# pokey.net
KiCad netlist of a schematic drawn in EAGLE
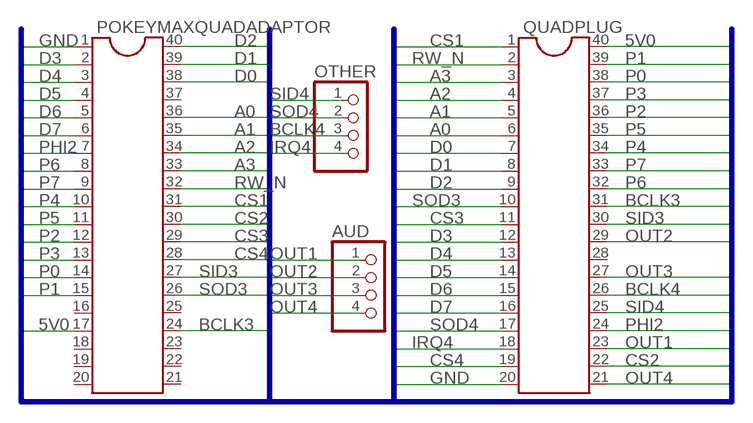
[diagram p0: schematic, sheet 1]

(export (version "E")
  (design (tool "Eeschema 10.0.6"))
  (components
    (comp (ref "AUD")
      (value "PINHD-1X4")
      (footprint "eagle-import:1X04")
      (libsource (lib "eagle-import") (part "PINHD-1X4"))
    )
    (comp (ref "OTHER")
      (value "PINHD-1X4")
      (footprint "eagle-import:1X04")
      (libsource (lib "eagle-import") (part "PINHD-1X4"))
    )
    (comp (ref "POKEYMAXQUADADAPTOR")
      (value "DIL40")
      (footprint "eagle-import:DIL40")
      (libsource (lib "eagle-import") (part "DIL40"))
    )
    (comp (ref "QUADPLUG")
      (value "DIL40")
      (footprint "eagle-import:DIL40")
      (libsource (lib "eagle-import") (part "DIL40"))
    )
  )
  (nets
    (net (code "1") (name "/5V0") (class "Default")
      (node (ref "POKEYMAXQUADADAPTOR") (pin "17") (pinfunction "17_17") (pintype "passive"))
      (node (ref "QUADPLUG") (pin "40") (pinfunction "40_40") (pintype "passive"))
    )
    (net (code "2") (name "/A0") (class "Default")
      (node (ref "POKEYMAXQUADADAPTOR") (pin "36") (pinfunction "36_36") (pintype "passive"))
      (node (ref "QUADPLUG") (pin "6") (pinfunction "6_6") (pintype "passive"))
    )
    (net (code "3") (name "/A1") (class "Default")
      (node (ref "POKEYMAXQUADADAPTOR") (pin "35") (pinfunction "35_35") (pintype "passive"))
      (node (ref "QUADPLUG") (pin "5") (pinfunction "5_5") (pintype "passive"))
    )
    (net (code "4") (name "/A2") (class "Default")
      (node (ref "POKEYMAXQUADADAPTOR") (pin "34") (pinfunction "34_34") (pintype "passive"))
      (node (ref "QUADPLUG") (pin "4") (pinfunction "4_4") (pintype "passive"))
    )
    (net (code "5") (name "/A3") (class "Default")
      (node (ref "POKEYMAXQUADADAPTOR") (pin "33") (pinfunction "33_33") (pintype "passive"))
      (node (ref "QUADPLUG") (pin "3") (pinfunction "3_3") (pintype "passive"))
    )
    (net (code "6") (name "/BCLK3") (class "Default")
      (node (ref "POKEYMAXQUADADAPTOR") (pin "24") (pinfunction "24_24") (pintype "passive"))
      (node (ref "QUADPLUG") (pin "31") (pinfunction "31_31") (pintype "passive"))
    )
    (net (code "7") (name "/BCLK4") (class "Default")
      (node (ref "OTHER") (pin "3") (pinfunction "3_3") (pintype "passive"))
      (node (ref "QUADPLUG") (pin "26") (pinfunction "26_26") (pintype "passive"))
    )
    (net (code "8") (name "/CS1") (class "Default")
      (node (ref "POKEYMAXQUADADAPTOR") (pin "31") (pinfunction "31_31") (pintype "passive"))
      (node (ref "QUADPLUG") (pin "1") (pinfunction "1_1") (pintype "passive"))
    )
    (net (code "9") (name "/CS2") (class "Default")
      (node (ref "POKEYMAXQUADADAPTOR") (pin "30") (pinfunction "30_30") (pintype "passive"))
      (node (ref "QUADPLUG") (pin "22") (pinfunction "22_22") (pintype "passive"))
    )
    (net (code "10") (name "/CS3") (class "Default")
      (node (ref "POKEYMAXQUADADAPTOR") (pin "29") (pinfunction "29_29") (pintype "passive"))
      (node (ref "QUADPLUG") (pin "11") (pinfunction "11_11") (pintype "passive"))
    )
    (net (code "11") (name "/CS4") (class "Default")
      (node (ref "POKEYMAXQUADADAPTOR") (pin "28") (pinfunction "28_28") (pintype "passive"))
      (node (ref "QUADPLUG") (pin "19") (pinfunction "19_19") (pintype "passive"))
    )
    (net (code "12") (name "/D0") (class "Default")
      (node (ref "POKEYMAXQUADADAPTOR") (pin "38") (pinfunction "38_38") (pintype "passive"))
      (node (ref "QUADPLUG") (pin "7") (pinfunction "7_7") (pintype "passive"))
    )
    (net (code "13") (name "/D1") (class "Default")
      (node (ref "POKEYMAXQUADADAPTOR") (pin "39") (pinfunction "39_39") (pintype "passive"))
      (node (ref "QUADPLUG") (pin "8") (pinfunction "8_8") (pintype "passive"))
    )
    (net (code "14") (name "/D2") (class "Default")
      (node (ref "POKEYMAXQUADADAPTOR") (pin "40") (pinfunction "40_40") (pintype "passive"))
      (node (ref "QUADPLUG") (pin "9") (pinfunction "9_9") (pintype "passive"))
    )
    (net (code "15") (name "/D3") (class "Default")
      (node (ref "POKEYMAXQUADADAPTOR") (pin "2") (pinfunction "2_2") (pintype "passive"))
      (node (ref "QUADPLUG") (pin "12") (pinfunction "12_12") (pintype "passive"))
    )
    (net (code "16") (name "/D4") (class "Default")
      (node (ref "POKEYMAXQUADADAPTOR") (pin "3") (pinfunction "3_3") (pintype "passive"))
      (node (ref "QUADPLUG") (pin "13") (pinfunction "13_13") (pintype "passive"))
    )
    (net (code "17") (name "/D5") (class "Default")
      (node (ref "POKEYMAXQUADADAPTOR") (pin "4") (pinfunction "4_4") (pintype "passive"))
      (node (ref "QUADPLUG") (pin "14") (pinfunction "14_14") (pintype "passive"))
    )
    (net (code "18") (name "/D6") (class "Default")
      (node (ref "POKEYMAXQUADADAPTOR") (pin "5") (pinfunction "5_5") (pintype "passive"))
      (node (ref "QUADPLUG") (pin "15") (pinfunction "15_15") (pintype "passive"))
    )
    (net (code "19") (name "/D7") (class "Default")
      (node (ref "POKEYMAXQUADADAPTOR") (pin "6") (pinfunction "6_6") (pintype "passive"))
      (node (ref "QUADPLUG") (pin "16") (pinfunction "16_16") (pintype "passive"))
    )
    (net (code "20") (name "/GND") (class "Default")
      (node (ref "POKEYMAXQUADADAPTOR") (pin "1") (pinfunction "1_1") (pintype "passive"))
      (node (ref "QUADPLUG") (pin "20") (pinfunction "20_20") (pintype "passive"))
    )
    (net (code "21") (name "/IRQ4") (class "Default")
      (node (ref "OTHER") (pin "4") (pinfunction "4_4") (pintype "passive"))
      (node (ref "QUADPLUG") (pin "18") (pinfunction "18_18") (pintype "passive"))
    )
    (net (code "22") (name "/OUT1") (class "Default")
      (node (ref "AUD") (pin "1") (pinfunction "1_1") (pintype "passive"))
      (node (ref "QUADPLUG") (pin "23") (pinfunction "23_23") (pintype "passive"))
    )
    (net (code "23") (name "/OUT2") (class "Default")
      (node (ref "AUD") (pin "2") (pinfunction "2_2") (pintype "passive"))
      (node (ref "QUADPLUG") (pin "29") (pinfunction "29_29") (pintype "passive"))
    )
    (net (code "24") (name "/OUT3") (class "Default")
      (node (ref "AUD") (pin "3") (pinfunction "3_3") (pintype "passive"))
      (node (ref "QUADPLUG") (pin "27") (pinfunction "27_27") (pintype "passive"))
    )
    (net (code "25") (name "/OUT4") (class "Default")
      (node (ref "AUD") (pin "4") (pinfunction "4_4") (pintype "passive"))
      (node (ref "QUADPLUG") (pin "21") (pinfunction "21_21") (pintype "passive"))
    )
    (net (code "26") (name "/P0") (class "Default")
      (node (ref "POKEYMAXQUADADAPTOR") (pin "14") (pinfunction "14_14") (pintype "passive"))
      (node (ref "QUADPLUG") (pin "38") (pinfunction "38_38") (pintype "passive"))
    )
    (net (code "27") (name "/P1") (class "Default")
      (node (ref "POKEYMAXQUADADAPTOR") (pin "15") (pinfunction "15_15") (pintype "passive"))
      (node (ref "QUADPLUG") (pin "39") (pinfunction "39_39") (pintype "passive"))
    )
    (net (code "28") (name "/P2") (class "Default")
      (node (ref "POKEYMAXQUADADAPTOR") (pin "12") (pinfunction "12_12") (pintype "passive"))
      (node (ref "QUADPLUG") (pin "36") (pinfunction "36_36") (pintype "passive"))
    )
    (net (code "29") (name "/P3") (class "Default")
      (node (ref "POKEYMAXQUADADAPTOR") (pin "13") (pinfunction "13_13") (pintype "passive"))
      (node (ref "QUADPLUG") (pin "37") (pinfunction "37_37") (pintype "passive"))
    )
    (net (code "30") (name "/P4") (class "Default")
      (node (ref "POKEYMAXQUADADAPTOR") (pin "10") (pinfunction "10_10") (pintype "passive"))
      (node (ref "QUADPLUG") (pin "34") (pinfunction "34_34") (pintype "passive"))
    )
    (net (code "31") (name "/P5") (class "Default")
      (node (ref "POKEYMAXQUADADAPTOR") (pin "11") (pinfunction "11_11") (pintype "passive"))
      (node (ref "QUADPLUG") (pin "35") (pinfunction "35_35") (pintype "passive"))
    )
    (net (code "32") (name "/P6") (class "Default")
      (node (ref "POKEYMAXQUADADAPTOR") (pin "8") (pinfunction "8_8") (pintype "passive"))
      (node (ref "QUADPLUG") (pin "32") (pinfunction "32_32") (pintype "passive"))
    )
    (net (code "33") (name "/P7") (class "Default")
      (node (ref "POKEYMAXQUADADAPTOR") (pin "9") (pinfunction "9_9") (pintype "passive"))
      (node (ref "QUADPLUG") (pin "33") (pinfunction "33_33") (pintype "passive"))
    )
    (net (code "34") (name "/PHI2") (class "Default")
      (node (ref "POKEYMAXQUADADAPTOR") (pin "7") (pinfunction "7_7") (pintype "passive"))
      (node (ref "QUADPLUG") (pin "24") (pinfunction "24_24") (pintype "passive"))
    )
    (net (code "35") (name "/RW_N") (class "Default")
      (node (ref "POKEYMAXQUADADAPTOR") (pin "32") (pinfunction "32_32") (pintype "passive"))
      (node (ref "QUADPLUG") (pin "2") (pinfunction "2_2") (pintype "passive"))
    )
    (net (code "36") (name "/SID3") (class "Default")
      (node (ref "POKEYMAXQUADADAPTOR") (pin "27") (pinfunction "27_27") (pintype "passive"))
      (node (ref "QUADPLUG") (pin "30") (pinfunction "30_30") (pintype "passive"))
    )
    (net (code "37") (name "/SID4") (class "Default")
      (node (ref "OTHER") (pin "1") (pinfunction "1_1") (pintype "passive"))
      (node (ref "QUADPLUG") (pin "25") (pinfunction "25_25") (pintype "passive"))
    )
    (net (code "38") (name "/SOD3") (class "Default")
      (node (ref "POKEYMAXQUADADAPTOR") (pin "26") (pinfunction "26_26") (pintype "passive"))
      (node (ref "QUADPLUG") (pin "10") (pinfunction "10_10") (pintype "passive"))
    )
    (net (code "39") (name "/SOD4") (class "Default")
      (node (ref "OTHER") (pin "2") (pinfunction "2_2") (pintype "passive"))
      (node (ref "QUADPLUG") (pin "17") (pinfunction "17_17") (pintype "passive"))
    )
    (net (code "40") (name "unconnected-(POKEYMAXQUADADAPTOR-Pad16)") (class "Default")
      (node (ref "POKEYMAXQUADADAPTOR") (pin "16") (pinfunction "16_16") (pintype "passive"))
    )
    (net (code "41") (name "unconnected-(POKEYMAXQUADADAPTOR-Pad18)") (class "Default")
      (node (ref "POKEYMAXQUADADAPTOR") (pin "18") (pinfunction "18_18") (pintype "passive"))
    )
    (net (code "42") (name "unconnected-(POKEYMAXQUADADAPTOR-Pad19)") (class "Default")
      (node (ref "POKEYMAXQUADADAPTOR") (pin "19") (pinfunction "19_19") (pintype "passive"))
    )
    (net (code "43") (name "unconnected-(POKEYMAXQUADADAPTOR-Pad20)") (class "Default")
      (node (ref "POKEYMAXQUADADAPTOR") (pin "20") (pinfunction "20_20") (pintype "passive"))
    )
    (net (code "44") (name "unconnected-(POKEYMAXQUADADAPTOR-Pad21)") (class "Default")
      (node (ref "POKEYMAXQUADADAPTOR") (pin "21") (pinfunction "21_21") (pintype "passive"))
    )
    (net (code "45") (name "unconnected-(POKEYMAXQUADADAPTOR-Pad22)") (class "Default")
      (node (ref "POKEYMAXQUADADAPTOR") (pin "22") (pinfunction "22_22") (pintype "passive"))
    )
    (net (code "46") (name "unconnected-(POKEYMAXQUADADAPTOR-Pad23)") (class "Default")
      (node (ref "POKEYMAXQUADADAPTOR") (pin "23") (pinfunction "23_23") (pintype "passive"))
    )
    (net (code "47") (name "unconnected-(POKEYMAXQUADADAPTOR-Pad25)") (class "Default")
      (node (ref "POKEYMAXQUADADAPTOR") (pin "25") (pinfunction "25_25") (pintype "passive"))
    )
    (net (code "48") (name "unconnected-(POKEYMAXQUADADAPTOR-Pad37)") (class "Default")
      (node (ref "POKEYMAXQUADADAPTOR") (pin "37") (pinfunction "37_37") (pintype "passive"))
    )
    (net (code "49") (name "unconnected-(QUADPLUG-Pad28)") (class "Default")
      (node (ref "QUADPLUG") (pin "28") (pinfunction "28_28") (pintype "passive"))
    )
  )
)
